# Power_Sensing.net
KiCad netlist of a schematic drawn in Altium Designer
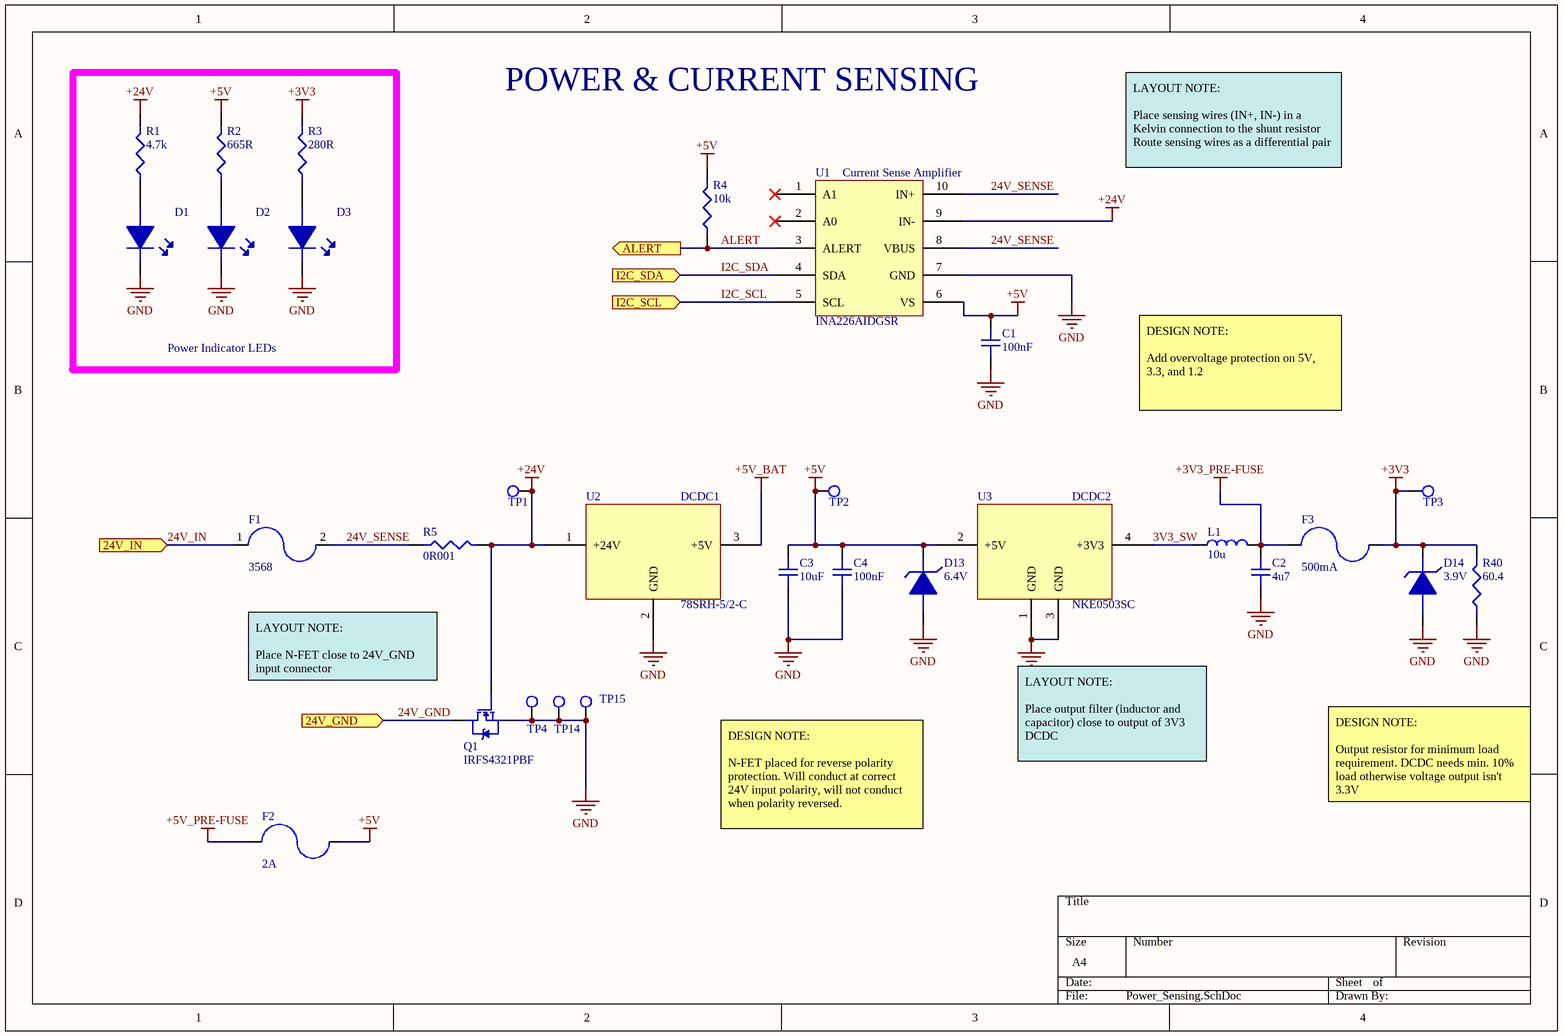
[diagram p0: Power_Sensing.SchDoc]

(export (version "E")
  (design (tool "Eeschema 10.0.6"))
  (components
    (comp (ref "C1")
      (value "100nF")
      (footprint "PHANTOM_FOOTPRINTS:C0805")
      (description "CAP MLCC 100nF 10Volts U2J 5%")
      (fields
        (field (name "MANUFACTURER") "Murata")
        (field (name "MANUFACTURER PART NUMBER") "GRM21B7U1A104JA01L")
      )
      (libsource (lib "PHANTOM_LIBRARY") (part "GRM21B7U1A104JA01L"))
    )
    (comp (ref "C2")
      (value "4u7")
      (footprint "C0805")
      (fields
        (field (name "MANUFACTURER") "Murata")
        (field (name "MANUFACTURER PART NUMBER") "GRM219R61A475KE34D")
        (field (name "TOLERANCE") "10%")
      )
      (libsource (lib "PHANTOM_LIBRARY") (part "GRM219R61A475KE34D"))
    )
    (comp (ref "C3")
      (value "10uF")
      (footprint "TANT_10u")
      (fields
        (field (name "MANUFACTURER") "Kyocera AVX")
        (field (name "MANUFACTURER PART NUMBER") "F381A106MMA")
        (field (name "TOLERANCE") "20%")
      )
      (libsource (lib "PHANTOM_LIBRARY") (part "F381A106MMA"))
    )
    (comp (ref "C4")
      (value "100nF")
      (footprint "PHANTOM_FOOTPRINTS:C0805")
      (description "CAP MLCC 100nF 10Volts U2J 5%")
      (fields
        (field (name "MANUFACTURER") "Murata")
        (field (name "MANUFACTURER PART NUMBER") "GRM21B7U1A104JA01L")
      )
      (libsource (lib "PHANTOM_LIBRARY") (part "GRM21B7U1A104JA01L"))
    )
    (comp (ref "D1")
      (value "LTST-C191KGKT")
      (footprint "LED_0603")
      (description "LED GREEN CLEAR 0603 SMD")
      (fields (field (name "MANUFACTURER") "Vishay Lite-On"))
      (libsource (lib "PHANTOM_LIBRARY") (part "LTST-C191KGKT"))
    )
    (comp (ref "D2")
      (value "LTST-C191KGKT")
      (footprint "LED_0603")
      (description "LED GREEN CLEAR 0603 SMD")
      (fields (field (name "MANUFACTURER") "Vishay Lite-On"))
      (libsource (lib "PHANTOM_LIBRARY") (part "LTST-C191KGKT"))
    )
    (comp (ref "D3")
      (value "LTST-C191KGKT")
      (footprint "LED_0603")
      (description "LED GREEN CLEAR 0603 SMD")
      (fields (field (name "MANUFACTURER") "Vishay Lite-On"))
      (libsource (lib "PHANTOM_LIBRARY") (part "LTST-C191KGKT"))
    )
    (comp (ref "D13")
      (value "6.4V")
      (footprint "DIODE_TVS")
      (description "DIODE TVS_6V4 5VWM 9.2VC SMA")
      (fields (field (name "MANUFACTURER") "Littelfuse") (field (name "MANUFACTURER PART NUMBER") "SMAJ5.0A"))
      (libsource (lib "PHANTOM_LIBRARY") (part "SMAJ5.0A"))
    )
    (comp (ref "D14")
      (value "3.9V")
      (footprint "DIODE_TVS")
      (description "DIODE ZENER 3.9V 1.5W SMA")
      (fields
        (field (name "MANUFACTURER") "ON Semiconductor")
        (field (name "MANUFACTURER PART NUMBER") "1SMA5915BT3G")
      )
      (libsource (lib "PHANTOM_LIBRARY") (part "1SMA5915BT3G"))
    )
    (comp (ref "F1")
      (value "3568")
      (footprint "FUSE_MINI_HOLDER")
      (description "FUSE HOLDER MINI AUTO PC")
      (fields (field (name "MANUFACTURER") "Keystone Electronics") (field (name "VOLTAGE") "500V"))
      (libsource (lib "PHANTOM_LIBRARY") (part "3568"))
    )
    (comp (ref "F2")
      (value "2A")
      (footprint "FUSE_0603")
      (description "FUSE_2A SMD 0603 LITTELFUSE")
      (fields
        (field (name "MANUFACTURER") "Littelfuse")
        (field (name "MANUFACTURER PART NUMBER") "0603SFV200F/32-2")
      )
      (libsource (lib "PHANTOM_LIBRARY") (part "0603SFV200F/32-2"))
    )
    (comp (ref "F3")
      (value "500mA")
      (footprint "FUSE_0603")
      (description "FUSE_0.5A SMD 0603, 0.5A")
      (fields
        (field (name "MANUFACTURER") "Panasonic ECG")
        (field (name "MANUFACTURER PART NUMBER") "ERB-RE0R50V")
      )
      (libsource (lib "PHANTOM_LIBRARY") (part "ERB-RE0R50V"))
    )
    (comp (ref "L1")
      (value "10u")
      (footprint "INDUCTOR")
      (description "Inductor Fixed 10uH 0.5A Mini SMT Power")
      (fields (field (name "MANUFACTURER") "Murata") (field (name "MANUFACTURER PART NUMBER") "82103C"))
      (libsource (lib "PHANTOM_LIBRARY") (part "82103C"))
    )
    (comp (ref "Q1")
      (value "IRFS4321PBF")
      (footprint "D2PAK_FETs")
      (description "MOSFET  N Channel, 83 A, 150 V, 0.012 ohm, 10 V, 5 V")
      (fields (field (name "MANUFACTURER") "Infineon"))
      (libsource (lib "PHANTOM_LIBRARY") (part "IRFS4321PBF"))
    )
    (comp (ref "R1")
      (value "4.7k")
      (footprint "R0805")
      (description "RES SMD 4.7K OHM 1% 1/8W 0805")
      (fields
        (field (name "MANUFACTURER") "Yageo")
        (field (name "MANUFACTURER PART NUMBER") "RC0805FR-074K7L")
      )
      (libsource (lib "PHANTOM_LIBRARY") (part "RC0805FR-074K7L"))
    )
    (comp (ref "R2")
      (value "665R")
      (footprint "R0805")
      (description "RES SMD 665 OHM 1% 1/8W 0805")
      (fields
        (field (name "MANUFACTURER") "Yageo")
        (field (name "MANUFACTURER PART NUMBER") "RC0805FR-07665RL")
      )
      (libsource (lib "PHANTOM_LIBRARY") (part "RC0805FR-07665RL"))
    )
    (comp (ref "R3")
      (value "280R")
      (footprint "R0805")
      (description "RES SMD 280 OHM 1% 1/8W 0805")
      (fields
        (field (name "MANUFACTURER") "Yageo")
        (field (name "MANUFACTURER PART NUMBER") "RC0805FR-07280RL")
      )
      (libsource (lib "PHANTOM_LIBRARY") (part "RC0805FR-07280RL"))
    )
    (comp (ref "R4")
      (value "10k")
      (footprint "R0805")
      (description "RES SMD 10K OHM 1% 1/8W 0805")
      (fields
        (field (name "MANUFACTURER") "Yageo Phycomp")
        (field (name "MANUFACTURER PART NUMBER") "RC0805FR-071KL")
      )
      (libsource (lib "PHANTOM_LIBRARY") (part "RC0805FR-071KL"))
    )
    (comp (ref "R5")
      (value "0R001")
      (footprint "R2512")
      (description "Res Thick Film 2512 0.001 Ohm 1% 1W 250ppm/C to 450ppm/C Molded SMD Embossed Carrier T/R")
      (fields
        (field (name "MANUFACTURER") "Panasonic ECG")
        (field (name "MANUFACTURER PART NUMBER") "ERJ-M1WTF1M0U")
      )
      (libsource (lib "PHANTOM_LIBRARY") (part "ERJ-M1WTF1M0U"))
    )
    (comp (ref "R40")
      (value "60.4")
      (footprint "R0805")
      (description "RES SMD 60.4 OHM 1% 1/8W 0805")
      (fields
        (field (name "MANUFACTURER") "Yageo")
        (field (name "MANUFACTURER PART NUMBER") "RC0805FR-0760R4L")
      )
      (libsource (lib "PHANTOM_LIBRARY") (part "RC0805FR-0760R4L"))
    )
    (comp (ref "TP1")
      (value "5015")
      (footprint "TP_HOOK")
      (description "TEST POINT, PCB, SMT")
      (fields (field (name "MANUFACTURER") "Keystone Electronics"))
      (libsource (lib "PHANTOM_LIBRARY") (part "5015"))
    )
    (comp (ref "TP2")
      (value "5015")
      (footprint "TP_HOOK")
      (description "TEST POINT, PCB, SMT")
      (fields (field (name "MANUFACTURER") "Keystone Electronics"))
      (libsource (lib "PHANTOM_LIBRARY") (part "5015"))
    )
    (comp (ref "TP3")
      (value "5015")
      (footprint "TP_HOOK")
      (description "TEST POINT, PCB, SMT")
      (fields (field (name "MANUFACTURER") "Keystone Electronics"))
      (libsource (lib "PHANTOM_LIBRARY") (part "5015"))
    )
    (comp (ref "TP4")
      (value "5015")
      (footprint "TP_HOOK")
      (description "TEST POINT, PCB, SMT")
      (fields (field (name "MANUFACTURER") "Keystone Electronics"))
      (libsource (lib "PHANTOM_LIBRARY") (part "5015"))
    )
    (comp (ref "TP14")
      (value "5015")
      (footprint "TP_HOOK")
      (description "TEST POINT, PCB, SMT")
      (fields (field (name "MANUFACTURER") "Keystone Electronics"))
      (libsource (lib "PHANTOM_LIBRARY") (part "5015"))
    )
    (comp (ref "TP15")
      (value "5015")
      (footprint "TP_HOOK")
      (description "TEST POINT, PCB, SMT")
      (fields (field (name "MANUFACTURER") "Keystone Electronics"))
      (libsource (lib "PHANTOM_LIBRARY") (part "5015"))
    )
    (comp (ref "U1")
      (value "INA226AIDGSR")
      (footprint "10-VSSOP_INA226")
      (description "IC MONITOR PWR/CURR BIDIR 10MSOP")
      (fields (field (name "MANUFACTURER") "Texas Instruments"))
      (libsource (lib "PHANTOM_LIBRARY") (part "INA226AIDGSR"))
    )
    (comp (ref "U2")
      (value "78SRH-5/2-C")
      (footprint "DCDC1")
      (description "DCDC 5V MURATA POWER SOLUTIONS 	   	78SRH-5/2-C 	   	IC, SYNC SWITCHING REGULATOR, TO-220-3")
      (fields (field (name "MANUFACTURER") "Murata"))
      (libsource (lib "PHANTOM_LIBRARY") (part "78SRH-5/2-C"))
    )
    (comp (ref "U3")
      (value "NKE0503SC")
      (footprint "DCDC2")
      (description "DCDC 3V3 CONVERTER 3.3V 1W")
      (fields (field (name "MANUFACTURER") "Murata"))
      (libsource (lib "PHANTOM_LIBRARY") (part "NKE0503SC"))
    )
  )
  (nets
    (net (code "1") (name "+3V3") (class "Default")
      (node (ref "D14") (pin "1") (pinfunction "1_1") (pintype "passive"))
      (node (ref "F3") (pin "2") (pinfunction "2_2") (pintype "passive"))
      (node (ref "R3") (pin "2") (pinfunction "2_2") (pintype "passive"))
      (node (ref "R40") (pin "2") (pinfunction "2_2") (pintype "passive"))
      (node (ref "TP3") (pin "1") (pinfunction "1_1") (pintype "passive"))
    )
    (net (code "2") (name "+3V3_PRE-FUSE") (class "Default")
      (node (ref "C2") (pin "2") (pinfunction "2_2") (pintype "passive"))
      (node (ref "F3") (pin "1") (pinfunction "1_1") (pintype "passive"))
      (node (ref "L1") (pin "2") (pinfunction "2_2") (pintype "passive"))
    )
    (net (code "3") (name "+5V") (class "Default")
      (node (ref "C1") (pin "2") (pinfunction "2_2") (pintype "passive"))
      (node (ref "C3") (pin "1") (pinfunction "1_1") (pintype "passive"))
      (node (ref "C4") (pin "2") (pinfunction "2_2") (pintype "passive"))
      (node (ref "D13") (pin "1") (pinfunction "1_1") (pintype "passive"))
      (node (ref "F2") (pin "2") (pinfunction "2_2") (pintype "passive"))
      (node (ref "R2") (pin "2") (pinfunction "2_2") (pintype "passive"))
      (node (ref "R4") (pin "2") (pinfunction "2_2") (pintype "passive"))
      (node (ref "TP2") (pin "1") (pinfunction "1_1") (pintype "passive"))
      (node (ref "U1") (pin "6") (pinfunction "VS_6") (pintype "passive"))
      (node (ref "U3") (pin "2") (pinfunction "+5V_2") (pintype "passive"))
    )
    (net (code "4") (name "+5V_BAT") (class "Default")
      (node (ref "U2") (pin "3") (pinfunction "+5V_3") (pintype "passive"))
    )
    (net (code "5") (name "+5V_PRE-FUSE") (class "Default")
      (node (ref "F2") (pin "1") (pinfunction "1_1") (pintype "passive"))
    )
    (net (code "6") (name "+24V") (class "Default")
      (node (ref "Q1") (pin "1") (pinfunction "1_1") (pintype "passive"))
      (node (ref "R1") (pin "2") (pinfunction "2_2") (pintype "passive"))
      (node (ref "R5") (pin "2") (pinfunction "2_2") (pintype "passive"))
      (node (ref "TP1") (pin "1") (pinfunction "1_1") (pintype "passive"))
      (node (ref "U1") (pin "9") (pinfunction "IN-_9") (pintype "passive"))
      (node (ref "U2") (pin "1") (pinfunction "+24V_1") (pintype "passive"))
    )
    (net (code "7") (name "/3V3_SW") (class "Default")
      (node (ref "L1") (pin "1") (pinfunction "1_1") (pintype "passive"))
      (node (ref "U3") (pin "4") (pinfunction "+3V3_4") (pintype "passive"))
    )
    (net (code "8") (name "/24V_GND") (class "Default")
      (node (ref "Q1") (pin "4") (pinfunction "4_4") (pintype "passive"))
    )
    (net (code "9") (name "/24V_IN") (class "Default")
      (node (ref "F1") (pin "1") (pinfunction "1_1") (pintype "passive"))
    )
    (net (code "10") (name "/24V_SENSE") (class "Default")
      (node (ref "F1") (pin "2") (pinfunction "2_2") (pintype "passive"))
      (node (ref "R5") (pin "1") (pinfunction "1_1") (pintype "passive"))
      (node (ref "U1") (pin "10") (pinfunction "IN+_10") (pintype "passive"))
      (node (ref "U1") (pin "8") (pinfunction "VBUS_8") (pintype "passive"))
    )
    (net (code "11") (name "/ALERT") (class "Default")
      (node (ref "R4") (pin "1") (pinfunction "1_1") (pintype "passive"))
      (node (ref "U1") (pin "3") (pinfunction "ALERT_3") (pintype "passive"))
    )
    (net (code "12") (name "/I2C_SCL") (class "Default")
      (node (ref "U1") (pin "5") (pinfunction "SCL_5") (pintype "passive"))
    )
    (net (code "13") (name "/I2C_SDA") (class "Default")
      (node (ref "U1") (pin "4") (pinfunction "SDA_4") (pintype "passive"))
    )
    (net (code "14") (name "GND") (class "Default")
      (node (ref "C1") (pin "1") (pinfunction "1_1") (pintype "passive"))
      (node (ref "C2") (pin "1") (pinfunction "1_1") (pintype "passive"))
      (node (ref "C3") (pin "2") (pinfunction "2_2") (pintype "passive"))
      (node (ref "C4") (pin "1") (pinfunction "1_1") (pintype "passive"))
      (node (ref "D1") (pin "2") (pinfunction "2_2") (pintype "passive"))
      (node (ref "D13") (pin "2") (pinfunction "2_2") (pintype "passive"))
      (node (ref "D14") (pin "2") (pinfunction "2_2") (pintype "passive"))
      (node (ref "D2") (pin "2") (pinfunction "2_2") (pintype "passive"))
      (node (ref "D3") (pin "2") (pinfunction "2_2") (pintype "passive"))
      (node (ref "Q1") (pin "3") (pinfunction "3_3") (pintype "passive"))
      (node (ref "R40") (pin "1") (pinfunction "1_1") (pintype "passive"))
      (node (ref "TP14") (pin "1") (pinfunction "1_1") (pintype "passive"))
      (node (ref "TP15") (pin "1") (pinfunction "1_1") (pintype "passive"))
      (node (ref "TP4") (pin "1") (pinfunction "1_1") (pintype "passive"))
      (node (ref "U1") (pin "7") (pinfunction "GND_7") (pintype "passive"))
      (node (ref "U2") (pin "2") (pinfunction "GND_2") (pintype "passive"))
      (node (ref "U3") (pin "1") (pinfunction "GND_1") (pintype "passive"))
      (node (ref "U3") (pin "3") (pinfunction "GND_3") (pintype "passive"))
    )
    (net (code "15") (name "Net-(D1-Pad1)") (class "Default")
      (node (ref "D1") (pin "1") (pinfunction "1_1") (pintype "passive"))
      (node (ref "R1") (pin "1") (pinfunction "1_1") (pintype "passive"))
    )
    (net (code "16") (name "Net-(D2-Pad1)") (class "Default")
      (node (ref "D2") (pin "1") (pinfunction "1_1") (pintype "passive"))
      (node (ref "R2") (pin "1") (pinfunction "1_1") (pintype "passive"))
    )
    (net (code "17") (name "Net-(D3-Pad1)") (class "Default")
      (node (ref "D3") (pin "1") (pinfunction "1_1") (pintype "passive"))
      (node (ref "R3") (pin "1") (pinfunction "1_1") (pintype "passive"))
    )
    (net (code "18") (name "unconnected-(U1-A0-Pad2)") (class "Default")
      (node (ref "U1") (pin "2") (pinfunction "A0_2") (pintype "passive+no_connect"))
    )
    (net (code "19") (name "unconnected-(U1-A1-Pad1)") (class "Default")
      (node (ref "U1") (pin "1") (pinfunction "A1_1") (pintype "passive+no_connect"))
    )
  )
)
